# TR_i3_6A_Module_v11.net
KiCad netlist of a schematic drawn in EAGLE
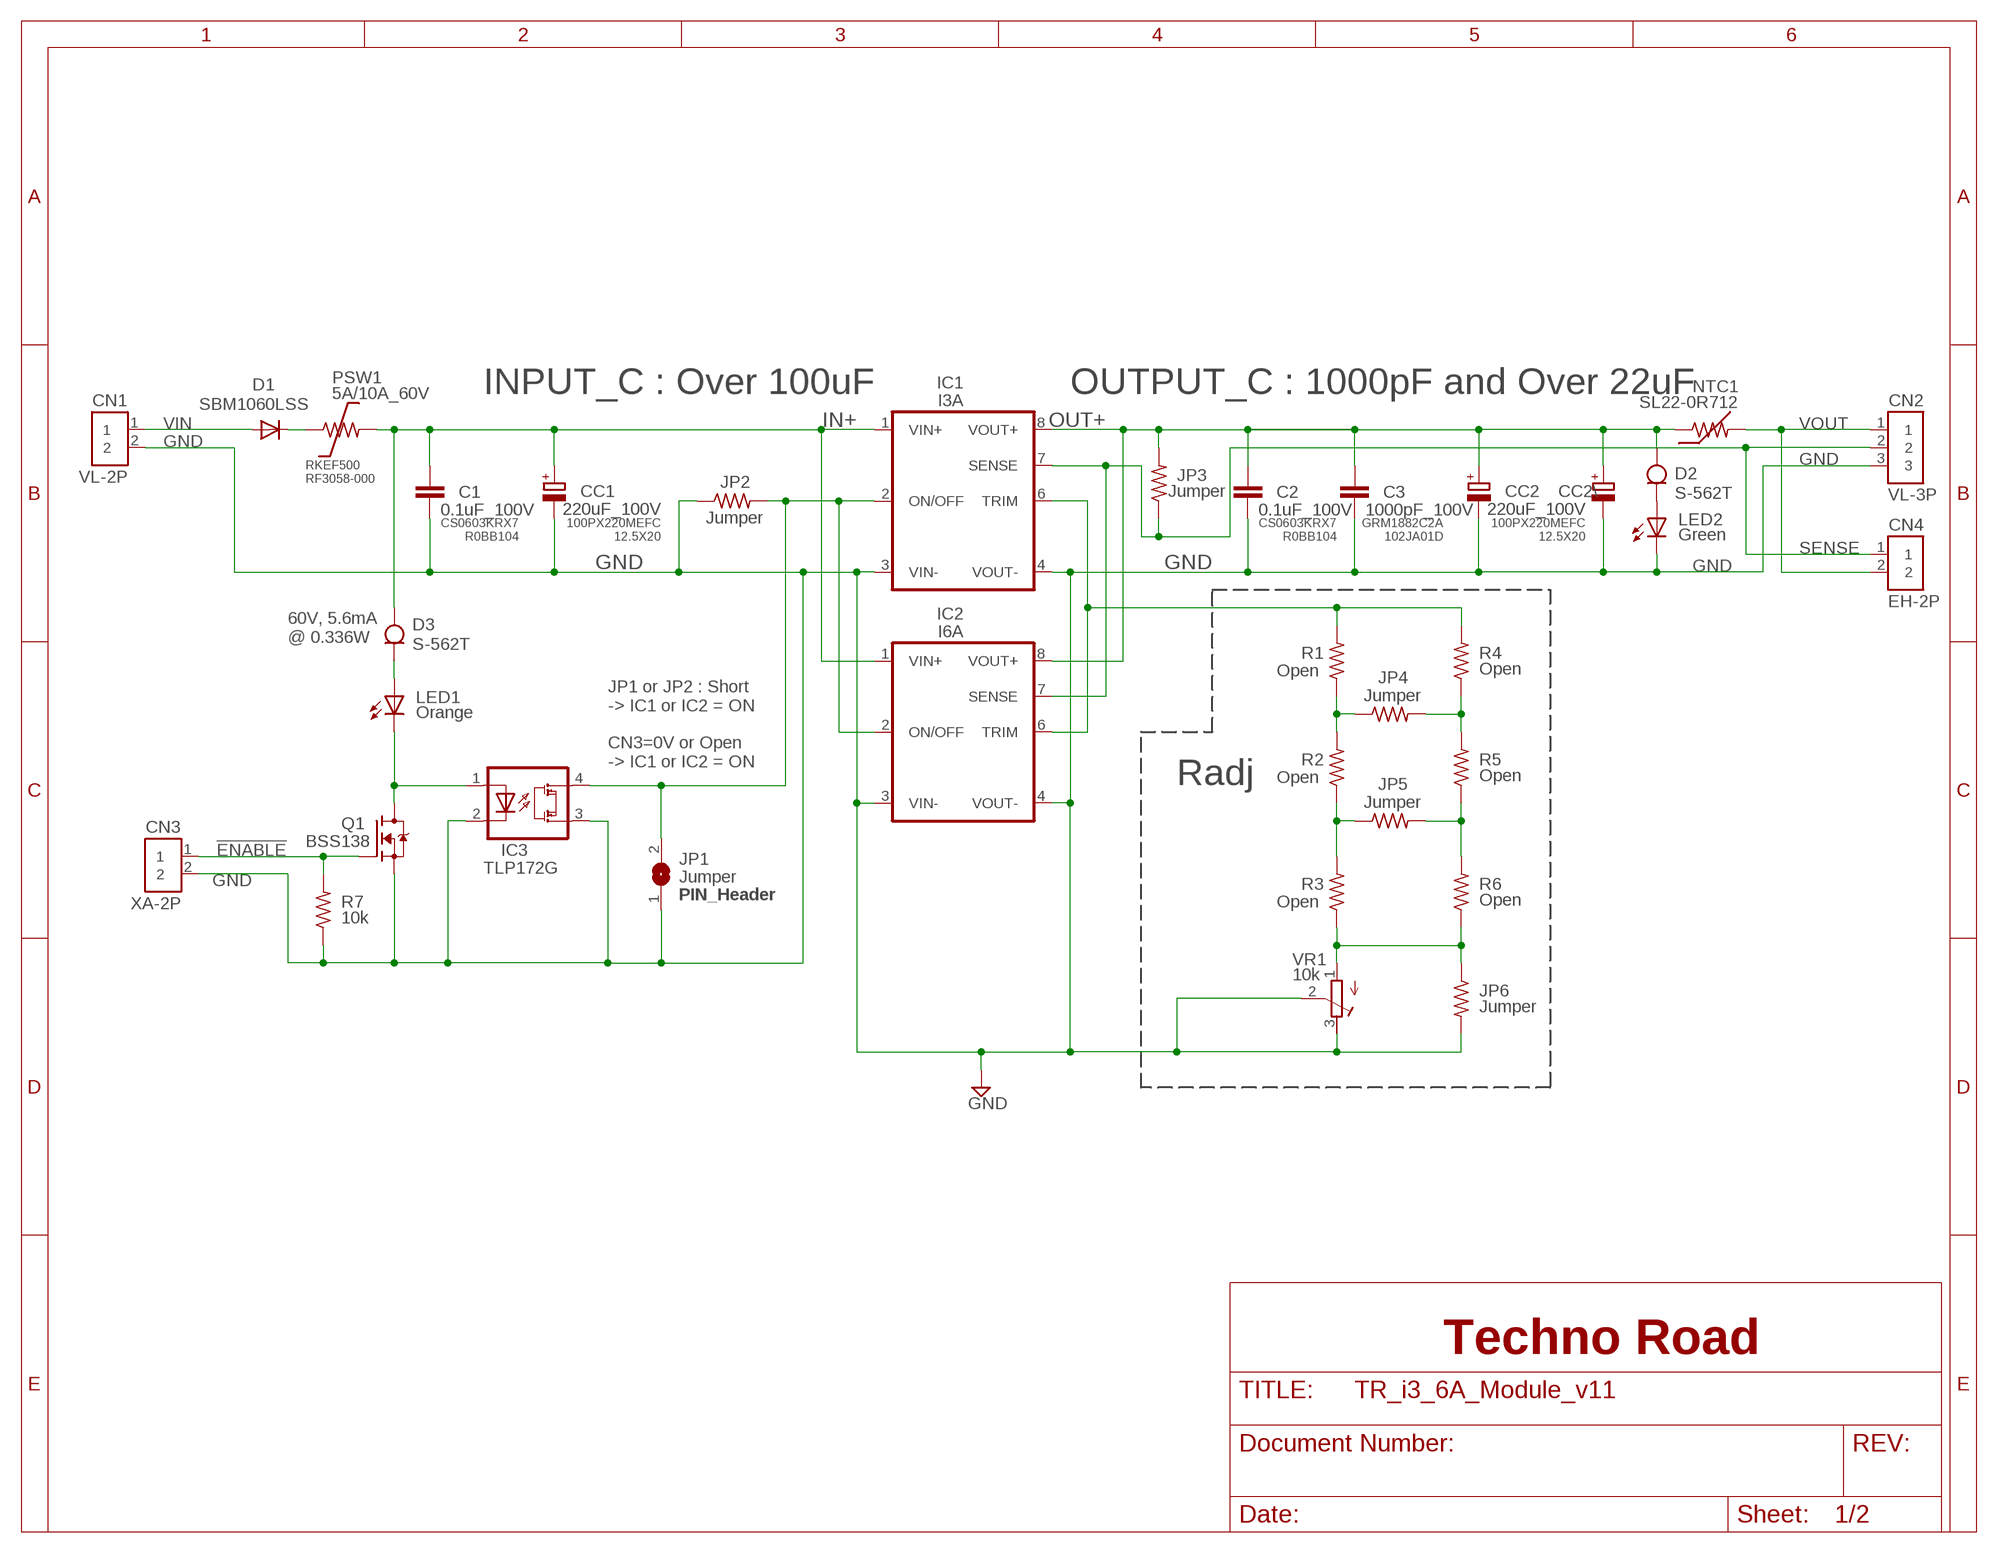
[diagram p0: schematic, sheet 1]

(export (version "E")
  (design (tool "Eeschema 10.0.6"))
  (components
    (comp (ref "C1")
      (value "0.1uF_100V")
      (footprint "eagle-import:C1608")
      (libsource (lib "eagle-import") (part "C1608"))
    )
    (comp (ref "C2")
      (value "0.1uF_100V")
      (footprint "eagle-import:C1608")
      (libsource (lib "eagle-import") (part "C1608"))
    )
    (comp (ref "C3")
      (value "1000pF_100V")
      (footprint "eagle-import:C1608")
      (libsource (lib "eagle-import") (part "C1608"))
    )
    (comp (ref "CC1")
      (value "220uF_100V")
      (footprint "eagle-import:CC0510")
      (libsource (lib "eagle-import") (part "CC0510"))
    )
    (comp (ref "CC2")
      (value "220uF_100V")
      (footprint "eagle-import:CC0510")
      (libsource (lib "eagle-import") (part "CC0510"))
    )
    (comp (ref "CC2\\")
      (value "CPOL-EUE7.5-16")
      (footprint "eagle-import:E7,5-16")
      (libsource (lib "eagle-import") (part "CPOL-EUE7.5-16"))
    )
    (comp (ref "CN1")
      (value "VL-2P")
      (footprint "eagle-import:VL3-2P")
      (libsource (lib "eagle-import") (part "2PVL3"))
    )
    (comp (ref "CN2")
      (value "VL-3P")
      (footprint "eagle-import:VL3-3P")
      (libsource (lib "eagle-import") (part "3PVL3"))
    )
    (comp (ref "CN3")
      (value "XA-2P")
      (footprint "eagle-import:XA-2P_NH")
      (libsource (lib "eagle-import") (part "2PXA_NH"))
    )
    (comp (ref "CN4")
      (value "EH-2P")
      (footprint "eagle-import:EH-2P")
      (libsource (lib "eagle-import") (part "2PEH"))
    )
    (comp (ref "D1")
      (value "SBM1060LSS")
      (footprint "eagle-import:12.7MM")
      (libsource (lib "eagle-import") (part "D12.7"))
    )
    (comp (ref "D2")
      (value "S-562T")
      (footprint "eagle-import:S-XXXT")
      (libsource (lib "eagle-import") (part "CRDS-XXXT"))
    )
    (comp (ref "D3")
      (value "S-562T")
      (footprint "eagle-import:S-XXXT")
      (libsource (lib "eagle-import") (part "CRDS-XXXT"))
    )
    (comp (ref "IC1")
      (value "I3A")
      (footprint "eagle-import:I3A_SERIES")
      (libsource (lib "eagle-import") (part "I3A/I6A_SEREISI3A"))
    )
    (comp (ref "IC2")
      (value "I6A")
      (footprint "eagle-import:I6A_SERIES")
      (libsource (lib "eagle-import") (part "I3A/I6A_SEREISI6A"))
    )
    (comp (ref "IC3")
      (value "TLP172G")
      (footprint "eagle-import:11-5H1")
      (libsource (lib "eagle-import") (part "TLP172"))
    )
    (comp (ref "JP1")
      (value "Jumper")
      (footprint "eagle-import:JP1D_HOLE")
      (libsource (lib "eagle-import") (part "JP1D"))
    )
    (comp (ref "JP2")
      (value "Jumper")
      (footprint "eagle-import:R1608_LARGE_PAD")
      (libsource (lib "eagle-import") (part "R1608_LARGE_PAD"))
    )
    (comp (ref "JP3")
      (value "Jumper")
      (footprint "eagle-import:R1608_LARGE_PAD")
      (libsource (lib "eagle-import") (part "R1608_LARGE_PAD"))
    )
    (comp (ref "JP4")
      (value "Jumper")
      (footprint "eagle-import:R1608_LARGE_PAD")
      (libsource (lib "eagle-import") (part "R1608_LARGE_PAD"))
    )
    (comp (ref "JP5")
      (value "Jumper")
      (footprint "eagle-import:R1608_LARGE_PAD")
      (libsource (lib "eagle-import") (part "R1608_LARGE_PAD"))
    )
    (comp (ref "JP6")
      (value "Jumper")
      (footprint "eagle-import:R1608_LARGE_PAD")
      (libsource (lib "eagle-import") (part "R1608_LARGE_PAD"))
    )
    (comp (ref "LED1")
      (value "Orange")
      (footprint "eagle-import:SML1608")
      (libsource (lib "eagle-import") (part "LEDSML0603"))
    )
    (comp (ref "LED2")
      (value "Green")
      (footprint "eagle-import:SML1608")
      (libsource (lib "eagle-import") (part "LEDSML0603"))
    )
    (comp (ref "NTC1")
      (value "SL22-0R712")
      (footprint "eagle-import:SL22")
      (libsource (lib "eagle-import") (part "NTCSL22"))
    )
    (comp (ref "PSW1")
      (value "5A/10A_60V")
      (footprint "eagle-import:PSW-10.16MM_4MM")
      (libsource (lib "eagle-import") (part "PSW10.16MM_4MM"))
    )
    (comp (ref "Q1")
      (value "BSS138")
      (footprint "eagle-import:SOT-23-3")
      (libsource (lib "eagle-import") (part "BSS138"))
    )
    (comp (ref "R1")
      (value "Open")
      (footprint "eagle-import:R1608_LARGE_PAD")
      (libsource (lib "eagle-import") (part "R1608_LARGE_PAD"))
    )
    (comp (ref "R2")
      (value "Open")
      (footprint "eagle-import:R1608_LARGE_PAD")
      (libsource (lib "eagle-import") (part "R1608_LARGE_PAD"))
    )
    (comp (ref "R3")
      (value "Open")
      (footprint "eagle-import:R1608_LARGE_PAD")
      (libsource (lib "eagle-import") (part "R1608_LARGE_PAD"))
    )
    (comp (ref "R4")
      (value "Open")
      (footprint "eagle-import:R1608_LARGE_PAD")
      (libsource (lib "eagle-import") (part "R1608_LARGE_PAD"))
    )
    (comp (ref "R5")
      (value "Open")
      (footprint "eagle-import:R1608_LARGE_PAD")
      (libsource (lib "eagle-import") (part "R1608_LARGE_PAD"))
    )
    (comp (ref "R6")
      (value "Open")
      (footprint "eagle-import:R1608_LARGE_PAD")
      (libsource (lib "eagle-import") (part "R1608_LARGE_PAD"))
    )
    (comp (ref "R7")
      (value "10k")
      (footprint "eagle-import:R1608_LARGE_PAD")
      (libsource (lib "eagle-import") (part "R1608_LARGE_PAD"))
    )
    (comp (ref "VR1")
      (value "10k")
      (footprint "eagle-import:3361P")
      (libsource (lib "eagle-import") (part "R-TRIM3361P"))
    )
  )
  (nets
    (net (code "1") (name "GND") (class "Default")
      (node (ref "C1") (pin "2") (pinfunction "2_2") (pintype "passive"))
      (node (ref "C2") (pin "2") (pinfunction "2_2") (pintype "passive"))
      (node (ref "C3") (pin "2") (pinfunction "2_2") (pintype "passive"))
      (node (ref "CC1") (pin "-") (pinfunction "-_-") (pintype "passive"))
      (node (ref "CC2") (pin "-") (pinfunction "-_-") (pintype "passive"))
      (node (ref "CC2\\") (pin "-") (pinfunction "-_-") (pintype "passive"))
      (node (ref "CN1") (pin "2") (pinfunction "2_2") (pintype "passive"))
      (node (ref "CN2") (pin "3") (pinfunction "3_3") (pintype "passive"))
      (node (ref "CN3") (pin "2") (pinfunction "2_2") (pintype "passive"))
      (node (ref "IC1") (pin "3") (pinfunction "VIN-_3") (pintype "passive"))
      (node (ref "IC1") (pin "4") (pinfunction "VOUT-_4") (pintype "passive"))
      (node (ref "IC2") (pin "3") (pinfunction "VIN-_3") (pintype "passive"))
      (node (ref "IC2") (pin "4") (pinfunction "VOUT-_4") (pintype "passive"))
      (node (ref "IC3") (pin "2") (pinfunction "C1_2") (pintype "passive"))
      (node (ref "IC3") (pin "3") (pinfunction "DRN1_3") (pintype "passive"))
      (node (ref "JP1") (pin "1") (pinfunction "1_1") (pintype "passive"))
      (node (ref "JP2") (pin "1") (pinfunction "1_1") (pintype "passive"))
      (node (ref "JP6") (pin "2") (pinfunction "2_2") (pintype "passive"))
      (node (ref "LED2") (pin "C") (pinfunction "C_C") (pintype "passive"))
      (node (ref "Q1") (pin "2") (pinfunction "S_2") (pintype "passive"))
      (node (ref "R7") (pin "1") (pinfunction "1_1") (pintype "passive"))
      (node (ref "VR1") (pin "2") (pinfunction "S_2") (pintype "passive"))
      (node (ref "VR1") (pin "3") (pinfunction "E_3") (pintype "passive"))
    )
    (net (code "2") (name "IN+") (class "Default")
      (node (ref "C1") (pin "1") (pinfunction "1_1") (pintype "passive"))
      (node (ref "CC1") (pin "+") (pinfunction "+_+") (pintype "passive"))
      (node (ref "D3") (pin "A") (pinfunction "A_A") (pintype "passive"))
      (node (ref "IC1") (pin "1") (pinfunction "VIN+_1") (pintype "passive"))
      (node (ref "IC2") (pin "1") (pinfunction "VIN+_1") (pintype "passive"))
      (node (ref "PSW1") (pin "2") (pinfunction "2_2") (pintype "passive"))
    )
    (net (code "3") (name "Net-(D1-C)") (class "Default")
      (node (ref "D1") (pin "2") (pinfunction "C_2") (pintype "passive"))
      (node (ref "PSW1") (pin "1") (pinfunction "1_1") (pintype "passive"))
    )
    (net (code "4") (name "Net-(D2-PadC)") (class "Default")
      (node (ref "D2") (pin "C") (pinfunction "C_C") (pintype "passive"))
      (node (ref "LED2") (pin "A") (pinfunction "A_A") (pintype "passive"))
    )
    (net (code "5") (name "Net-(D3-PadC)") (class "Default")
      (node (ref "D3") (pin "C") (pinfunction "C_C") (pintype "passive"))
      (node (ref "LED1") (pin "A") (pinfunction "A_A") (pintype "passive"))
    )
    (net (code "6") (name "Net-(IC1-ON{slash}OFF)") (class "Default")
      (node (ref "IC1") (pin "2") (pinfunction "ON/OFF_2") (pintype "input"))
      (node (ref "IC2") (pin "2") (pinfunction "ON/OFF_2") (pintype "input"))
      (node (ref "IC3") (pin "4") (pinfunction "DRN2_4") (pintype "passive"))
      (node (ref "JP1") (pin "2") (pinfunction "2_2") (pintype "passive"))
      (node (ref "JP2") (pin "2") (pinfunction "2_2") (pintype "passive"))
    )
    (net (code "7") (name "Net-(IC1-TRIM)") (class "Default")
      (node (ref "IC1") (pin "6") (pinfunction "TRIM_6") (pintype "input"))
      (node (ref "IC2") (pin "6") (pinfunction "TRIM_6") (pintype "input"))
      (node (ref "R1") (pin "2") (pinfunction "2_2") (pintype "passive"))
      (node (ref "R4") (pin "2") (pinfunction "2_2") (pintype "passive"))
    )
    (net (code "8") (name "Net-(IC3-A1)") (class "Default")
      (node (ref "IC3") (pin "1") (pinfunction "A1_1") (pintype "passive"))
      (node (ref "LED1") (pin "C") (pinfunction "C_C") (pintype "passive"))
      (node (ref "Q1") (pin "3") (pinfunction "D_3") (pintype "passive"))
    )
    (net (code "9") (name "Net-(JP4-Pad1)") (class "Default")
      (node (ref "JP4") (pin "1") (pinfunction "1_1") (pintype "passive"))
      (node (ref "R1") (pin "1") (pinfunction "1_1") (pintype "passive"))
      (node (ref "R2") (pin "2") (pinfunction "2_2") (pintype "passive"))
    )
    (net (code "10") (name "Net-(JP4-Pad2)") (class "Default")
      (node (ref "JP4") (pin "2") (pinfunction "2_2") (pintype "passive"))
      (node (ref "R4") (pin "1") (pinfunction "1_1") (pintype "passive"))
      (node (ref "R5") (pin "2") (pinfunction "2_2") (pintype "passive"))
    )
    (net (code "11") (name "Net-(JP5-Pad1)") (class "Default")
      (node (ref "JP5") (pin "1") (pinfunction "1_1") (pintype "passive"))
      (node (ref "R2") (pin "1") (pinfunction "1_1") (pintype "passive"))
      (node (ref "R3") (pin "2") (pinfunction "2_2") (pintype "passive"))
    )
    (net (code "12") (name "Net-(JP5-Pad2)") (class "Default")
      (node (ref "JP5") (pin "2") (pinfunction "2_2") (pintype "passive"))
      (node (ref "R5") (pin "1") (pinfunction "1_1") (pintype "passive"))
      (node (ref "R6") (pin "2") (pinfunction "2_2") (pintype "passive"))
    )
    (net (code "13") (name "Net-(VR1-A)") (class "Default")
      (node (ref "JP6") (pin "1") (pinfunction "1_1") (pintype "passive"))
      (node (ref "R3") (pin "1") (pinfunction "1_1") (pintype "passive"))
      (node (ref "R6") (pin "1") (pinfunction "1_1") (pintype "passive"))
      (node (ref "VR1") (pin "1") (pinfunction "A_1") (pintype "passive"))
    )
    (net (code "14") (name "OUT+") (class "Default")
      (node (ref "C2") (pin "1") (pinfunction "1_1") (pintype "passive"))
      (node (ref "C3") (pin "1") (pinfunction "1_1") (pintype "passive"))
      (node (ref "CC2") (pin "+") (pinfunction "+_+") (pintype "passive"))
      (node (ref "CC2\\") (pin "+") (pinfunction "+_+") (pintype "passive"))
      (node (ref "D2") (pin "A") (pinfunction "A_A") (pintype "passive"))
      (node (ref "IC1") (pin "8") (pinfunction "VOUT+_8") (pintype "passive"))
      (node (ref "IC2") (pin "8") (pinfunction "VOUT+_8") (pintype "passive"))
      (node (ref "JP3") (pin "2") (pinfunction "2_2") (pintype "passive"))
      (node (ref "NTC1") (pin "1") (pinfunction "1_1") (pintype "passive"))
    )
    (net (code "15") (name "SENSE") (class "Default")
      (node (ref "CN2") (pin "2") (pinfunction "2_2") (pintype "passive"))
      (node (ref "CN4") (pin "1") (pinfunction "1_1") (pintype "passive"))
      (node (ref "IC1") (pin "7") (pinfunction "SENSE_7") (pintype "passive"))
      (node (ref "IC2") (pin "7") (pinfunction "SENSE_7") (pintype "passive"))
      (node (ref "JP3") (pin "1") (pinfunction "1_1") (pintype "passive"))
    )
    (net (code "16") (name "VIN") (class "Default")
      (node (ref "CN1") (pin "1") (pinfunction "1_1") (pintype "passive"))
      (node (ref "D1") (pin "1") (pinfunction "A_1") (pintype "passive"))
    )
    (net (code "17") (name "VOUT") (class "Default")
      (node (ref "CN2") (pin "1") (pinfunction "1_1") (pintype "passive"))
      (node (ref "CN4") (pin "2") (pinfunction "2_2") (pintype "passive"))
      (node (ref "NTC1") (pin "2") (pinfunction "2_2") (pintype "passive"))
    )
    (net (code "18") (name "~{ENABLE}") (class "Default")
      (node (ref "CN3") (pin "1") (pinfunction "1_1") (pintype "passive"))
      (node (ref "Q1") (pin "1") (pinfunction "G_1") (pintype "passive"))
      (node (ref "R7") (pin "2") (pinfunction "2_2") (pintype "passive"))
    )
  )
)
